# 464421_22-01_RF_OUT.net
KiCad netlist of a schematic drawn in Altium Designer
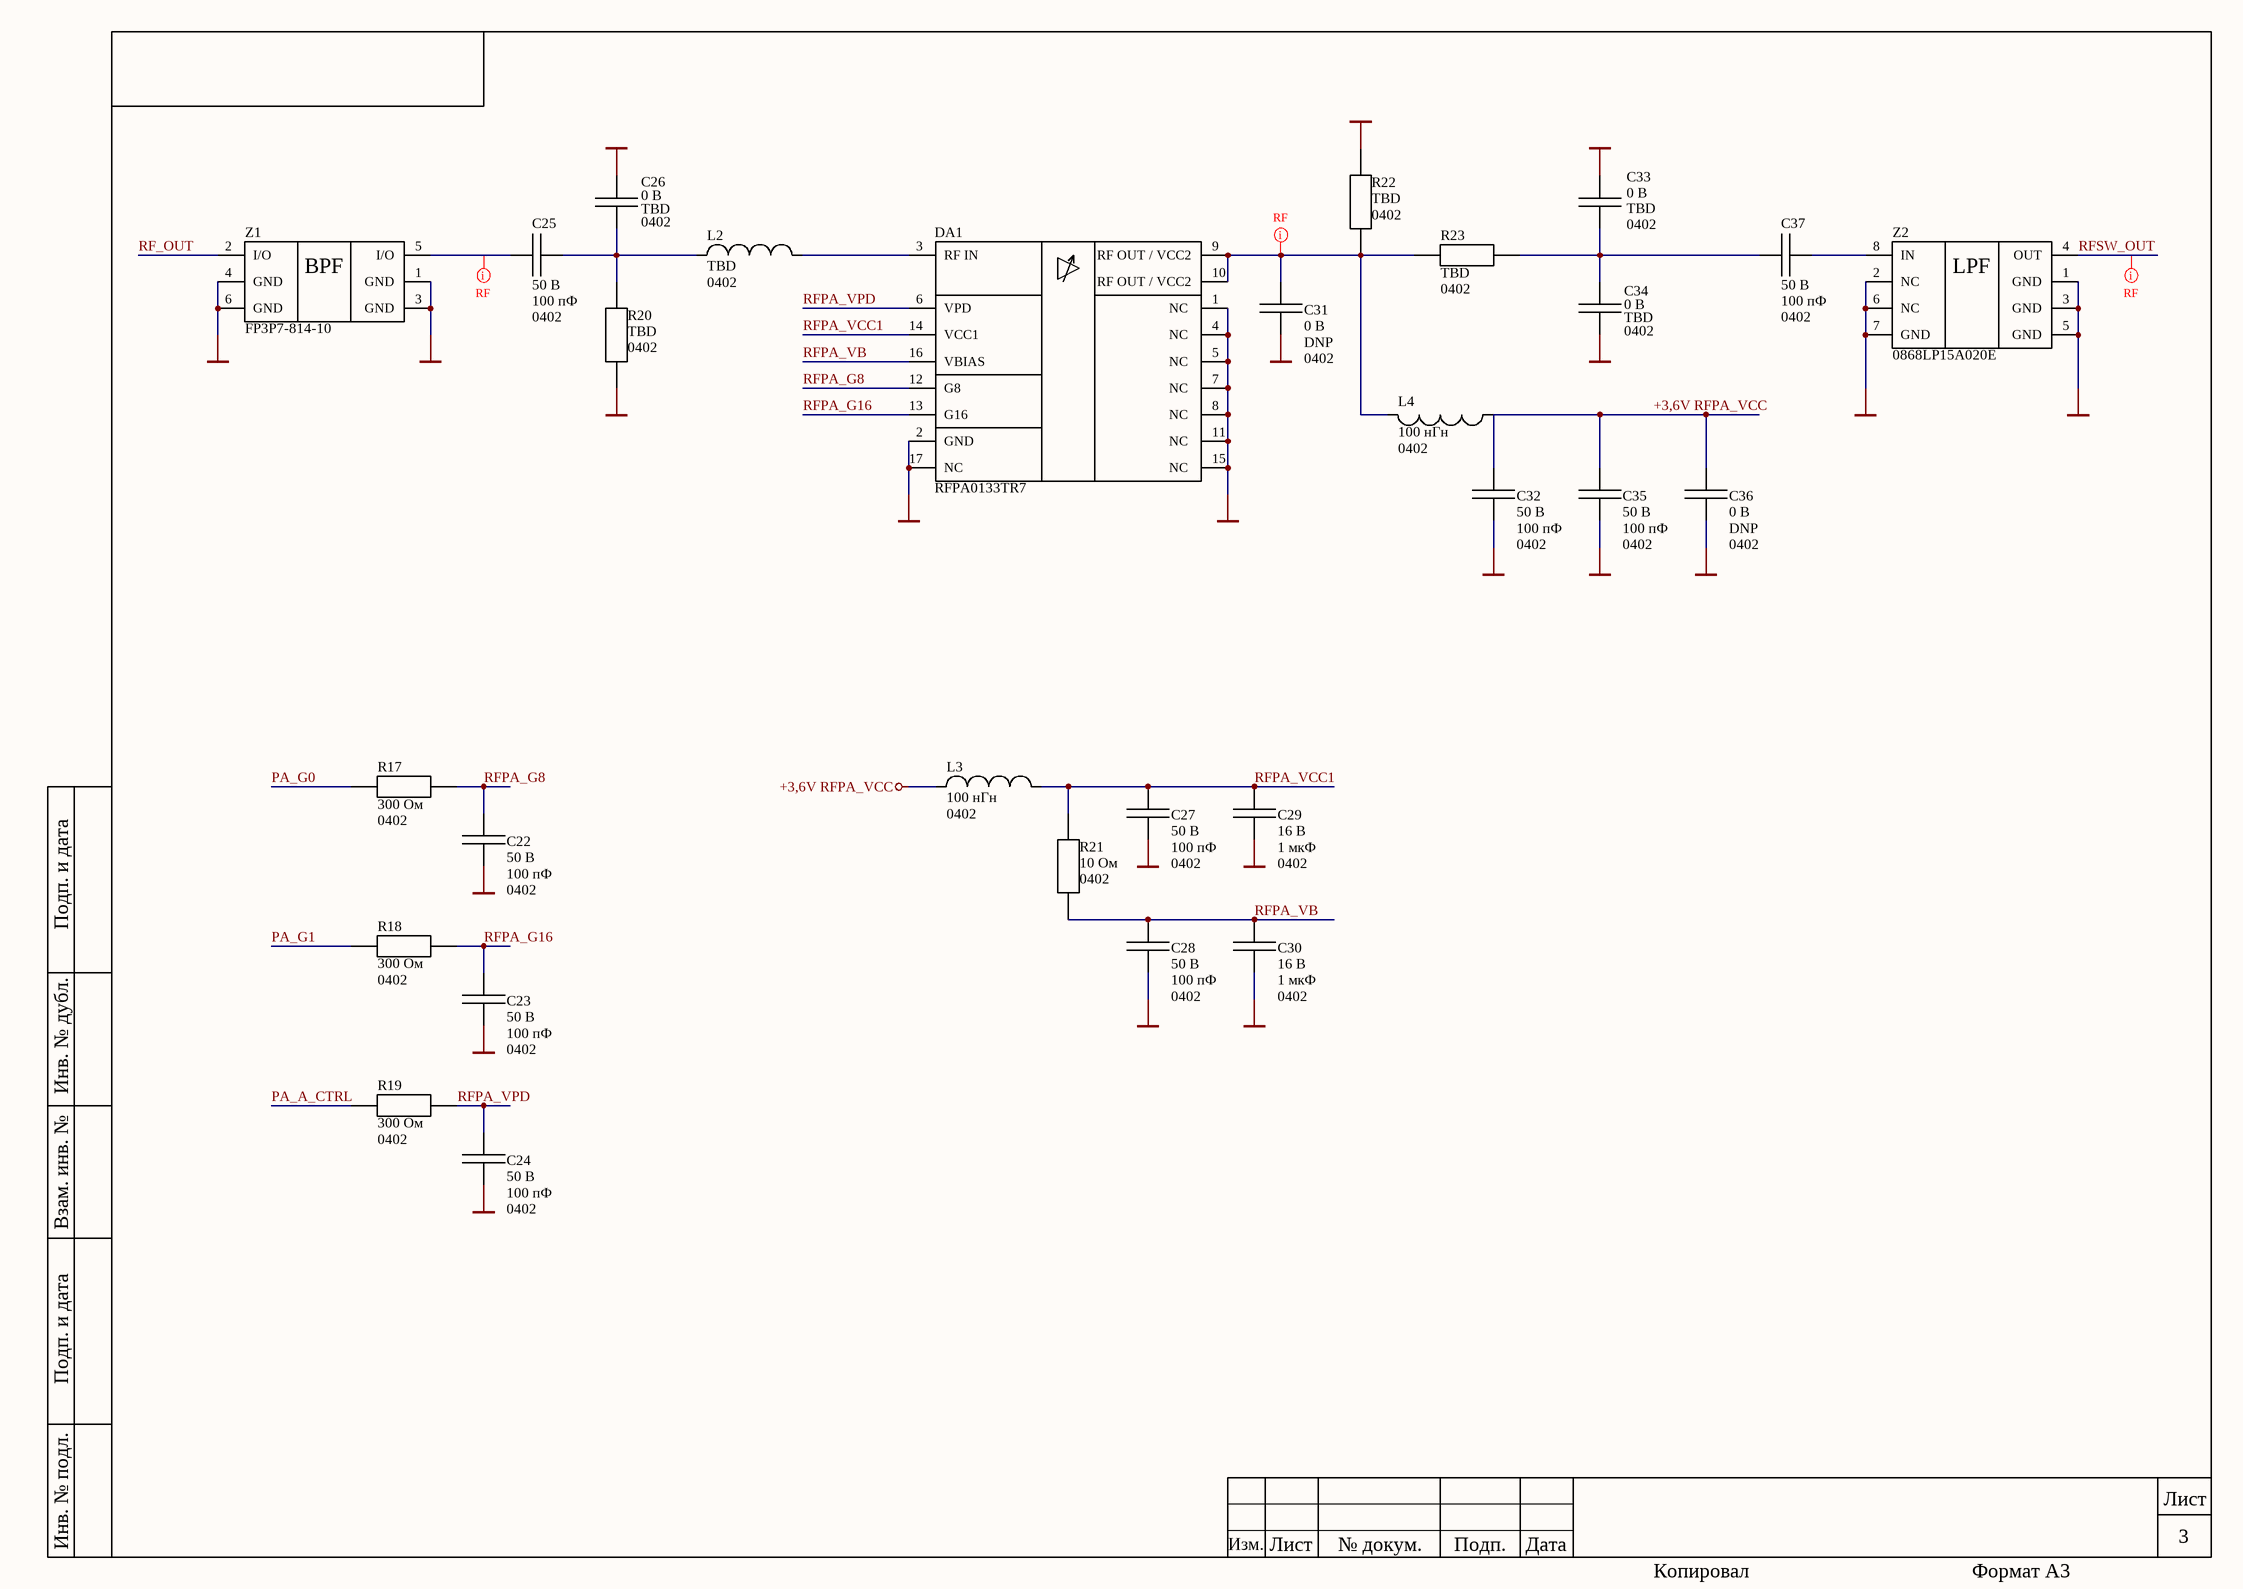
[diagram p0: МПСУ.464421.22-01 RF_OUT.SchDoc]

(export (version "E")
  (design (tool "Eeschema 10.0.6"))
  (components
    (comp (ref "C22")
      (value "100 пФ")
      (footprint "Passive_V2_0:CAPC100X50X55L20N")
      (description "Capacitor 0402")
      (fields
        (field (name "PARTNUMBER") "GRM1555C1H101JZ01D")
        (field (name "MANUFACTURER") "Murata")
        (field (name "PEAK_CONDITION") "50 В")
        (field (name "PACKAGE") "0402")
        (field (name "DESIGNER") "Свидерский")
      )
      (libsource (lib "Passive_V2_0") (part "C 0402"))
    )
    (comp (ref "C23")
      (value "100 пФ")
      (footprint "Passive_V2_0:CAPC100X50X55L20N")
      (description "Capacitor 0402")
      (fields
        (field (name "PARTNUMBER") "GRM1555C1H101JZ01D")
        (field (name "MANUFACTURER") "Murata")
        (field (name "PEAK_CONDITION") "50 В")
        (field (name "PACKAGE") "0402")
        (field (name "DESIGNER") "Свидерский")
      )
      (libsource (lib "Passive_V2_0") (part "C 0402"))
    )
    (comp (ref "C24")
      (value "100 пФ")
      (footprint "Passive_V2_0:CAPC100X50X55L20N")
      (description "Capacitor 0402")
      (fields
        (field (name "PARTNUMBER") "GRM1555C1H101JZ01D")
        (field (name "MANUFACTURER") "Murata")
        (field (name "PEAK_CONDITION") "50 В")
        (field (name "PACKAGE") "0402")
        (field (name "DESIGNER") "Свидерский")
      )
      (libsource (lib "Passive_V2_0") (part "C 0402"))
    )
    (comp (ref "C25")
      (value "100 пФ")
      (footprint "Passive_V2_0:CAPC100X50X55L20N")
      (description "Capacitor 0402")
      (fields
        (field (name "PARTNUMBER") "GRM1555C1H101JZ01D")
        (field (name "MANUFACTURER") "Murata")
        (field (name "PEAK_CONDITION") "50 В")
        (field (name "PACKAGE") "0402")
        (field (name "DESIGNER") "Свидерский")
      )
      (libsource (lib "Passive_V2_0") (part "C 0402"))
    )
    (comp (ref "C26")
      (value "TBD")
      (footprint "Passive_V2_0:CAPC100X50X55L20N")
      (description "Capacitor 0402")
      (fields
        (field (name "TOLERANCE") "0 %")
        (field (name "PEAK_CONDITION") "0 В")
        (field (name "PACKAGE") "0402")
        (field (name "Comment") "TBD 0402")
        (field (name "DESIGNER") "Свидерский")
      )
      (libsource (lib "Passive_V2_0") (part "C 0402"))
    )
    (comp (ref "C27")
      (value "100 пФ")
      (footprint "Passive_V2_0:CAPC100X50X55L20N")
      (description "Capacitor 0402")
      (fields
        (field (name "PARTNUMBER") "GRM1555C1H101JZ01D")
        (field (name "MANUFACTURER") "Murata")
        (field (name "PEAK_CONDITION") "50 В")
        (field (name "PACKAGE") "0402")
        (field (name "DESIGNER") "Свидерский")
      )
      (libsource (lib "Passive_V2_0") (part "C 0402"))
    )
    (comp (ref "C28")
      (value "100 пФ")
      (footprint "Passive_V2_0:CAPC100X50X55L20N")
      (description "Capacitor 0402")
      (fields
        (field (name "PARTNUMBER") "GRM1555C1H101JZ01D")
        (field (name "MANUFACTURER") "Murata")
        (field (name "PEAK_CONDITION") "50 В")
        (field (name "PACKAGE") "0402")
        (field (name "DESIGNER") "Свидерский")
      )
      (libsource (lib "Passive_V2_0") (part "C 0402"))
    )
    (comp (ref "C29")
      (value "1 мкФ")
      (footprint "Passive_V2_0:CAPC100X50X55L20N")
      (description "Capacitor 0402")
      (fields
        (field (name "PARTNUMBER") "GRM155R61C105KA12D")
        (field (name "MANUFACTURER") "Murata")
        (field (name "PEAK_CONDITION") "16 В")
        (field (name "PACKAGE") "0402")
        (field (name "DESIGNER") "Свидерский")
      )
      (libsource (lib "Passive_V2_0") (part "C 0402"))
    )
    (comp (ref "C30")
      (value "1 мкФ")
      (footprint "Passive_V2_0:CAPC100X50X55L20N")
      (description "Capacitor 0402")
      (fields
        (field (name "PARTNUMBER") "GRM155R61C105KA12D")
        (field (name "MANUFACTURER") "Murata")
        (field (name "PEAK_CONDITION") "16 В")
        (field (name "PACKAGE") "0402")
        (field (name "DESIGNER") "Свидерский")
      )
      (libsource (lib "Passive_V2_0") (part "C 0402"))
    )
    (comp (ref "C31")
      (value "DNP")
      (footprint "Passive_V2_0:CAPC100X50X55L20N")
      (description "Capacitor 0402")
      (fields
        (field (name "TOLERANCE") "0 %")
        (field (name "PEAK_CONDITION") "0 В")
        (field (name "PACKAGE") "0402")
        (field (name "Comment") "DNP 0402")
        (field (name "DESIGNER") "Свидерский")
      )
      (libsource (lib "Passive_V2_0") (part "C 0402"))
    )
    (comp (ref "C32")
      (value "100 пФ")
      (footprint "Passive_V2_0:CAPC100X50X55L20N")
      (description "Capacitor 0402")
      (fields
        (field (name "PARTNUMBER") "GRM1555C1H101JZ01D")
        (field (name "MANUFACTURER") "Murata")
        (field (name "PEAK_CONDITION") "50 В")
        (field (name "PACKAGE") "0402")
        (field (name "DESIGNER") "Свидерский")
      )
      (libsource (lib "Passive_V2_0") (part "C 0402"))
    )
    (comp (ref "C33")
      (value "TBD")
      (footprint "Passive_V2_0:CAPC100X50X55L20N")
      (description "Capacitor 0402")
      (fields
        (field (name "TOLERANCE") "0 %")
        (field (name "PEAK_CONDITION") "0 В")
        (field (name "PACKAGE") "0402")
        (field (name "Comment") "TBD 0402")
        (field (name "DESIGNER") "Свидерский")
      )
      (libsource (lib "Passive_V2_0") (part "C 0402"))
    )
    (comp (ref "C34")
      (value "TBD")
      (footprint "Passive_V2_0:CAPC100X50X55L20N")
      (description "Capacitor 0402")
      (fields
        (field (name "TOLERANCE") "0 %")
        (field (name "PEAK_CONDITION") "0 В")
        (field (name "PACKAGE") "0402")
        (field (name "Comment") "TBD 0402")
        (field (name "DESIGNER") "Свидерский")
      )
      (libsource (lib "Passive_V2_0") (part "C 0402"))
    )
    (comp (ref "C35")
      (value "100 пФ")
      (footprint "Passive_V2_0:CAPC100X50X55L20N")
      (description "Capacitor 0402")
      (fields
        (field (name "PARTNUMBER") "GRM1555C1H101JZ01D")
        (field (name "MANUFACTURER") "Murata")
        (field (name "PEAK_CONDITION") "50 В")
        (field (name "PACKAGE") "0402")
        (field (name "DESIGNER") "Свидерский")
      )
      (libsource (lib "Passive_V2_0") (part "C 0402"))
    )
    (comp (ref "C36")
      (value "DNP")
      (footprint "Passive_V2_0:CAPC100X50X55L20N")
      (description "Capacitor 0402")
      (fields
        (field (name "TOLERANCE") "0 %")
        (field (name "PEAK_CONDITION") "0 В")
        (field (name "PACKAGE") "0402")
        (field (name "Comment") "DNP 0402")
        (field (name "DESIGNER") "Свидерский")
      )
      (libsource (lib "Passive_V2_0") (part "C 0402"))
    )
    (comp (ref "C37")
      (value "100 пФ")
      (footprint "Passive_V2_0:CAPC100X50X55L20N")
      (description "Capacitor 0402")
      (fields
        (field (name "PARTNUMBER") "GRM1555C1H101JZ01D")
        (field (name "MANUFACTURER") "Murata")
        (field (name "PEAK_CONDITION") "50 В")
        (field (name "PACKAGE") "0402")
        (field (name "DESIGNER") "Свидерский")
      )
      (libsource (lib "Passive_V2_0") (part "C 0402"))
    )
    (comp (ref "DA1")
      (value "RFPA0133TR7")
      (footprint "IC_V2_0:QFN50P300X300X90_HS-17N")
      (description "380 to 960 MHz, 3 to 5V programmable gain high efficiency power amplifier")
      (fields
        (field (name "MANUFACTURER") "RFD, Qorvo")
        (field (name "PARTNUMBER") "RFPA0133TR7")
        (field (name "DESIGNER") "Лазба")
      )
      (libsource (lib "IC_V2_0") (part "RFPA0133TR7"))
    )
    (comp (ref "L2")
      (value "TBD")
      (footprint "Passive_V2_0:INDC100X50X60L10N")
      (description "Inductor 0402")
      (fields
        (field (name "TOLERANCE") "0 %")
        (field (name "PACKAGE") "0402")
        (field (name "Comment") "TBD 0402")
        (field (name "DESIGNER") "Свидерский")
      )
      (libsource (lib "Passive_V2_0") (part "L 0402"))
    )
    (comp (ref "L3")
      (value "100 нГн")
      (footprint "Passive_V2_0:INDC100X50X60L10N")
      (description "Inductor 0402")
      (fields
        (field (name "PARTNUMBER") "LQG15HNR10J02D")
        (field (name "TOLERANCE") "5 %")
        (field (name "PACKAGE") "0402")
        (field (name "DESIGNER") "Свидерский")
      )
      (libsource (lib "Passive_V2_0") (part "L 0402"))
    )
    (comp (ref "L4")
      (value "100 нГн")
      (footprint "Passive_V2_0:INDC100X50X60L10N")
      (description "Inductor 0402")
      (fields
        (field (name "PARTNUMBER") "LQG15HNR10J02D")
        (field (name "TOLERANCE") "5 %")
        (field (name "PACKAGE") "0402")
        (field (name "DESIGNER") "Свидерский")
      )
      (libsource (lib "Passive_V2_0") (part "L 0402"))
    )
    (comp (ref "R17")
      (value "300 Ом")
      (footprint "Passive_V2_0:RESC100X50X40L25N")
      (description "Resistor 0402")
      (fields
        (field (name "PARTNUMBER") "RI0402L301JT")
        (field (name "TOLERANCE") "5 %")
        (field (name "PACKAGE") "0402")
        (field (name "DESIGNER") "Свидерский")
      )
      (libsource (lib "") (part "R 0402_2"))
    )
    (comp (ref "R18")
      (value "300 Ом")
      (footprint "Passive_V2_0:RESC100X50X40L25N")
      (description "Resistor 0402")
      (fields
        (field (name "PARTNUMBER") "RI0402L301JT")
        (field (name "TOLERANCE") "5 %")
        (field (name "PACKAGE") "0402")
        (field (name "DESIGNER") "Свидерский")
      )
      (libsource (lib "") (part "R 0402_2"))
    )
    (comp (ref "R19")
      (value "300 Ом")
      (footprint "Passive_V2_0:RESC100X50X40L25N")
      (description "Resistor 0402")
      (fields
        (field (name "PARTNUMBER") "RI0402L301JT")
        (field (name "TOLERANCE") "5 %")
        (field (name "PACKAGE") "0402")
        (field (name "DESIGNER") "Свидерский")
      )
      (libsource (lib "") (part "R 0402_2"))
    )
    (comp (ref "R20")
      (value "TBD")
      (footprint "Passive_V2_0:RESC100X50X40L25N")
      (description "Resistor 0402")
      (fields
        (field (name "TOLERANCE") "0 %")
        (field (name "PACKAGE") "0402")
        (field (name "Comment") "TBD 0402")
        (field (name "DESIGNER") "Свидерский")
      )
      (libsource (lib "") (part "R 0402_1"))
    )
    (comp (ref "R21")
      (value "10 Ом")
      (footprint "Passive_V2_0:RESC100X50X40L25N")
      (description "Resistor 0402")
      (fields
        (field (name "PARTNUMBER") "RI0402L100JT")
        (field (name "TOLERANCE") "5 %")
        (field (name "PACKAGE") "0402")
        (field (name "DESIGNER") "Свидерский")
      )
      (libsource (lib "") (part "R 0402_1"))
    )
    (comp (ref "R22")
      (value "TBD")
      (footprint "Passive_V2_0:RESC100X50X40L25N")
      (description "Resistor 0402")
      (fields
        (field (name "TOLERANCE") "0 %")
        (field (name "PACKAGE") "0402")
        (field (name "Comment") "TBD 0402")
        (field (name "DESIGNER") "Свидерский")
      )
      (libsource (lib "Passive_V2_0") (part "R 0402"))
    )
    (comp (ref "R23")
      (value "TBD")
      (footprint "Passive_V2_0:RESC100X50X40L25N")
      (description "Resistor 0402")
      (fields
        (field (name "TOLERANCE") "0 %")
        (field (name "PACKAGE") "0402")
        (field (name "Comment") "TBD 0402")
        (field (name "DESIGNER") "Свидерский")
      )
      (libsource (lib "") (part "R 0402_2"))
    )
    (comp (ref "Z1")
      (value "FP3P7-814-10")
      (footprint "Passive_V2_0:LCCS110P300X300X146-6N")
      (description "BandPass Filter")
      (fields
        (field (name "MANUFACTURER") "БУТИС")
        (field (name "PARTNUMBER") "FP3P7-814-10")
        (field (name "DESIGNER") "Лазба")
      )
      (libsource (lib "Passive_V2_0") (part "FP3P7-***-**"))
    )
    (comp (ref "Z2")
      (value "0868LP15A020E")
      (footprint "Passive_V2_0:LCC065P125X200X085-8")
      (fields
        (field (name "MANUFACTURER") "Johanson Technology Inc.")
        (field (name "PARTNUMBER") "0868LP15A020E")
        (field (name "DESIGNER") "Лазба")
      )
      (libsource (lib "Passive_V2_0") (part "0868LP15A020"))
    )
  )
  (nets
    (net (code "1") (name "+3,6V RFPA_VCC") (class "Default")
      (node (ref "C32") (pin "1") (pinfunction "1_1") (pintype "passive"))
      (node (ref "C35") (pin "1") (pinfunction "1_1") (pintype "passive"))
      (node (ref "C36") (pin "1") (pinfunction "1_1") (pintype "passive"))
      (node (ref "L3") (pin "1") (pinfunction "1_1") (pintype "passive"))
      (node (ref "L4") (pin "1") (pinfunction "1_1") (pintype "passive"))
    )
    (net (code "2") (name "/PA_A_CTRL") (class "Default")
      (node (ref "R19") (pin "1") (pinfunction "1_1") (pintype "passive"))
    )
    (net (code "3") (name "/PA_G0") (class "Default")
      (node (ref "R17") (pin "1") (pinfunction "1_1") (pintype "passive"))
    )
    (net (code "4") (name "/PA_G1") (class "Default")
      (node (ref "R18") (pin "1") (pinfunction "1_1") (pintype "passive"))
    )
    (net (code "5") (name "/RFPA_G8") (class "Default")
      (node (ref "C22") (pin "2") (pinfunction "2_2") (pintype "passive"))
      (node (ref "DA1") (pin "12") (pinfunction "G8_12") (pintype "passive"))
      (node (ref "R17") (pin "2") (pinfunction "2_2") (pintype "passive"))
    )
    (net (code "6") (name "/RFPA_G16") (class "Default")
      (node (ref "C23") (pin "2") (pinfunction "2_2") (pintype "passive"))
      (node (ref "DA1") (pin "13") (pinfunction "G16_13") (pintype "passive"))
      (node (ref "R18") (pin "2") (pinfunction "2_2") (pintype "passive"))
    )
    (net (code "7") (name "/RFPA_VB") (class "Default")
      (node (ref "C28") (pin "2") (pinfunction "2_2") (pintype "passive"))
      (node (ref "C30") (pin "2") (pinfunction "2_2") (pintype "passive"))
      (node (ref "DA1") (pin "16") (pinfunction "VBIAS_16") (pintype "passive"))
      (node (ref "R21") (pin "2") (pinfunction "2_2") (pintype "passive"))
    )
    (net (code "8") (name "/RFPA_VPD") (class "Default")
      (node (ref "C24") (pin "2") (pinfunction "2_2") (pintype "passive"))
      (node (ref "DA1") (pin "6") (pinfunction "VPD_6") (pintype "passive"))
      (node (ref "R19") (pin "2") (pinfunction "2_2") (pintype "passive"))
    )
    (net (code "9") (name "/RFPA_VСС1") (class "Default")
      (node (ref "C27") (pin "2") (pinfunction "2_2") (pintype "passive"))
      (node (ref "C29") (pin "2") (pinfunction "2_2") (pintype "passive"))
      (node (ref "DA1") (pin "14") (pinfunction "VCC1_14") (pintype "passive"))
      (node (ref "L3") (pin "2") (pinfunction "2_2") (pintype "passive"))
      (node (ref "R21") (pin "1") (pinfunction "1_1") (pintype "passive"))
    )
    (net (code "10") (name "/RFSW_OUT") (class "Default")
      (node (ref "Z2") (pin "4") (pinfunction "OUT_4") (pintype "passive"))
    )
    (net (code "11") (name "/RF_OUT") (class "Default")
      (node (ref "Z1") (pin "2") (pinfunction "I/O_2") (pintype "passive"))
    )
    (net (code "12") (name "GND") (class "Default")
      (node (ref "C22") (pin "1") (pinfunction "1_1") (pintype "passive"))
      (node (ref "C23") (pin "1") (pinfunction "1_1") (pintype "passive"))
      (node (ref "C24") (pin "1") (pinfunction "1_1") (pintype "passive"))
      (node (ref "C26") (pin "2") (pinfunction "2_2") (pintype "passive"))
      (node (ref "C27") (pin "1") (pinfunction "1_1") (pintype "passive"))
      (node (ref "C28") (pin "1") (pinfunction "1_1") (pintype "passive"))
      (node (ref "C29") (pin "1") (pinfunction "1_1") (pintype "passive"))
      (node (ref "C30") (pin "1") (pinfunction "1_1") (pintype "passive"))
      (node (ref "C31") (pin "2") (pinfunction "2_2") (pintype "passive"))
      (node (ref "C32") (pin "2") (pinfunction "2_2") (pintype "passive"))
      (node (ref "C33") (pin "2") (pinfunction "2_2") (pintype "passive"))
      (node (ref "C34") (pin "2") (pinfunction "2_2") (pintype "passive"))
      (node (ref "C35") (pin "2") (pinfunction "2_2") (pintype "passive"))
      (node (ref "C36") (pin "2") (pinfunction "2_2") (pintype "passive"))
      (node (ref "DA1") (pin "1") (pinfunction "NC_1") (pintype "passive"))
      (node (ref "DA1") (pin "11") (pinfunction "NC_11") (pintype "passive"))
      (node (ref "DA1") (pin "15") (pinfunction "NC_15") (pintype "passive"))
      (node (ref "DA1") (pin "17") (pinfunction "NC_17") (pintype "passive"))
      (node (ref "DA1") (pin "2") (pinfunction "GND_2") (pintype "passive"))
      (node (ref "DA1") (pin "4") (pinfunction "NC_4") (pintype "passive"))
      (node (ref "DA1") (pin "5") (pinfunction "NC_5") (pintype "passive"))
      (node (ref "DA1") (pin "7") (pinfunction "NC_7") (pintype "passive"))
      (node (ref "DA1") (pin "8") (pinfunction "NC_8") (pintype "passive"))
      (node (ref "R20") (pin "2") (pinfunction "2_2") (pintype "passive"))
      (node (ref "R22") (pin "2") (pinfunction "2_2") (pintype "passive"))
      (node (ref "Z1") (pin "1") (pinfunction "GND_1") (pintype "passive"))
      (node (ref "Z1") (pin "3") (pinfunction "GND_3") (pintype "passive"))
      (node (ref "Z1") (pin "4") (pinfunction "GND_4") (pintype "passive"))
      (node (ref "Z1") (pin "6") (pinfunction "GND_6") (pintype "passive"))
      (node (ref "Z2") (pin "1") (pinfunction "GND_1") (pintype "passive"))
      (node (ref "Z2") (pin "2") (pinfunction "NC_2") (pintype "passive"))
      (node (ref "Z2") (pin "3") (pinfunction "GND_3") (pintype "passive"))
      (node (ref "Z2") (pin "5") (pinfunction "GND_5") (pintype "passive"))
      (node (ref "Z2") (pin "6") (pinfunction "NC_6") (pintype "passive"))
      (node (ref "Z2") (pin "7") (pinfunction "GND_7") (pintype "passive"))
    )
    (net (code "13") (name "Net-(C25-Pad1)") (class "Default")
      (node (ref "C25") (pin "1") (pinfunction "1_1") (pintype "passive"))
      (node (ref "Z1") (pin "5") (pinfunction "I/O_5") (pintype "passive"))
    )
    (net (code "14") (name "Net-(C25-Pad2)") (class "Default")
      (node (ref "C25") (pin "2") (pinfunction "2_2") (pintype "passive"))
      (node (ref "C26") (pin "1") (pinfunction "1_1") (pintype "passive"))
      (node (ref "L2") (pin "1") (pinfunction "1_1") (pintype "passive"))
      (node (ref "R20") (pin "1") (pinfunction "1_1") (pintype "passive"))
    )
    (net (code "15") (name "Net-(C31-Pad1)") (class "Default")
      (node (ref "C31") (pin "1") (pinfunction "1_1") (pintype "passive"))
      (node (ref "DA1") (pin "10") (pinfunction "RF_OUT_/_VCC2_10") (pintype "passive"))
      (node (ref "DA1") (pin "9") (pinfunction "RF_OUT_/_VCC2_9") (pintype "passive"))
      (node (ref "L4") (pin "2") (pinfunction "2_2") (pintype "passive"))
      (node (ref "R22") (pin "1") (pinfunction "1_1") (pintype "passive"))
      (node (ref "R23") (pin "1") (pinfunction "1_1") (pintype "passive"))
    )
    (net (code "16") (name "Net-(C33-Pad1)") (class "Default")
      (node (ref "C33") (pin "1") (pinfunction "1_1") (pintype "passive"))
      (node (ref "C34") (pin "1") (pinfunction "1_1") (pintype "passive"))
      (node (ref "C37") (pin "1") (pinfunction "1_1") (pintype "passive"))
      (node (ref "R23") (pin "2") (pinfunction "2_2") (pintype "passive"))
    )
    (net (code "17") (name "Net-(DA1-RF_IN)") (class "Default")
      (node (ref "DA1") (pin "3") (pinfunction "RF_IN_3") (pintype "passive"))
      (node (ref "L2") (pin "2") (pinfunction "2_2") (pintype "passive"))
    )
    (net (code "18") (name "Net-(Z2-IN)") (class "Default")
      (node (ref "C37") (pin "2") (pinfunction "2_2") (pintype "passive"))
      (node (ref "Z2") (pin "8") (pinfunction "IN_8") (pintype "passive"))
    )
  )
)
